# DMX512_6A.net
KiCad netlist of a schematic drawn in Altium Designer
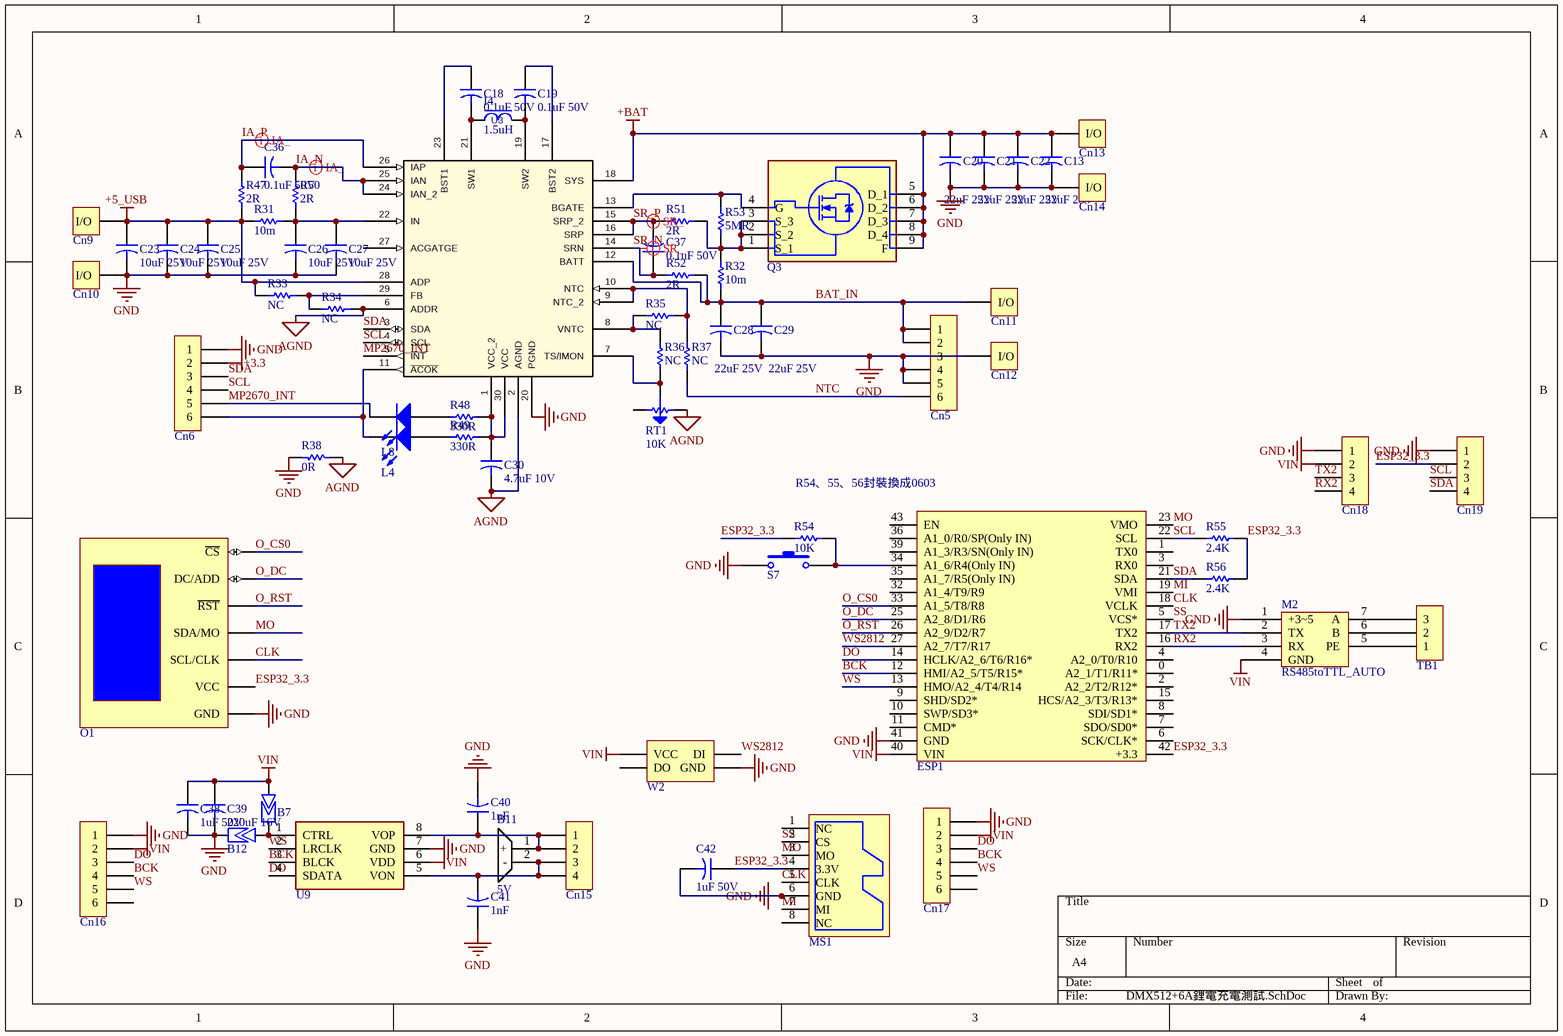
[diagram p0: DMX512+6A鋰電充電測試.SchDoc]

(export (version "E")
  (design (tool "Eeschema 10.0.6"))
  (components
    (comp (ref "B7")
      (value "不上錫")
      (footprint "BYPASS-0402")
      (description "短路焊點")
      (libsource (lib "MyLibray") (part "Bypass"))
    )
    (comp (ref "B11")
      (value "5V")
      (footprint "Buzzer_12085")
      (description "無源蜂鳴器")
      (libsource (lib "MyLibray") (part "Buzzer"))
    )
    (comp (ref "B12")
      (value "上錫")
      (footprint "BYPASS-0402")
      (description "短路焊點")
      (libsource (lib "MyLibray") (part "Bypass"))
    )
    (comp (ref "C13")
      (value "22uF 25V")
      (footprint "Cap SMD-0805")
      (description "電容")
      (libsource (lib "MyLibray") (part "Cap"))
    )
    (comp (ref "C18")
      (value "0.1uF 50V")
      (footprint "Cap SMD-0603")
      (description "電容")
      (libsource (lib "MyLibray") (part "Cap"))
    )
    (comp (ref "C19")
      (value "0.1uF 50V")
      (footprint "Cap SMD-0603")
      (description "電容")
      (libsource (lib "MyLibray") (part "Cap"))
    )
    (comp (ref "C20")
      (value "22uF 25V")
      (footprint "Cap SMD-0805")
      (description "電容")
      (libsource (lib "MyLibray") (part "Cap"))
    )
    (comp (ref "C21")
      (value "22uF 25V")
      (footprint "Cap SMD-0805")
      (description "電容")
      (libsource (lib "MyLibray") (part "Cap"))
    )
    (comp (ref "C22")
      (value "22uF 25V")
      (footprint "Cap SMD-0805")
      (description "電容")
      (libsource (lib "MyLibray") (part "Cap"))
    )
    (comp (ref "C23")
      (value "10uF 25V")
      (footprint "Cap SMD-0805")
      (description "電容")
      (libsource (lib "MyLibray") (part "Cap"))
    )
    (comp (ref "C24")
      (value "10uF 25V")
      (footprint "Cap SMD-0805")
      (description "電容")
      (libsource (lib "MyLibray") (part "Cap"))
    )
    (comp (ref "C25")
      (value "10uF 25V")
      (footprint "Cap SMD-0805")
      (description "電容")
      (libsource (lib "MyLibray") (part "Cap"))
    )
    (comp (ref "C26")
      (value "10uF 25V")
      (footprint "Cap SMD-0805")
      (description "電容")
      (libsource (lib "MyLibray") (part "Cap"))
    )
    (comp (ref "C27")
      (value "10uF 25V")
      (footprint "Cap SMD-0805")
      (description "電容")
      (libsource (lib "MyLibray") (part "Cap"))
    )
    (comp (ref "C28")
      (value "22uF 25V")
      (footprint "Cap SMD-0805")
      (description "電容")
      (libsource (lib "MyLibray") (part "Cap"))
    )
    (comp (ref "C29")
      (value "22uF 25V")
      (footprint "Cap SMD-0805")
      (description "電容")
      (libsource (lib "MyLibray") (part "Cap"))
    )
    (comp (ref "C30")
      (value "4.7uF 10V")
      (footprint "Cap SMD-0603")
      (description "電容")
      (libsource (lib "MyLibray") (part "Cap"))
    )
    (comp (ref "C36")
      (value "0.1uF 50V")
      (footprint "Cap SMD-0603")
      (description "電容")
      (libsource (lib "MyLibray") (part "Cap"))
    )
    (comp (ref "C37")
      (value "0.1uF 50V")
      (footprint "Cap SMD-0603")
      (description "電容")
      (libsource (lib "MyLibray") (part "Cap"))
    )
    (comp (ref "C38")
      (value "1uF 50V")
      (footprint "Cap SMD-0603")
      (description "電容")
      (libsource (lib "MyLibray") (part "Cap"))
    )
    (comp (ref "C39")
      (value "220uF 16V")
      (footprint "CAP SMD-B3528")
      (description "電容")
      (libsource (lib "MyLibray") (part "Cap"))
    )
    (comp (ref "C40")
      (value "1nF")
      (footprint "Cap SMD-0603")
      (description "電容")
      (libsource (lib "MyLibray") (part "Cap"))
    )
    (comp (ref "C41")
      (value "1nF")
      (footprint "Cap SMD-0603")
      (description "電容")
      (libsource (lib "MyLibray") (part "Cap"))
    )
    (comp (ref "C42")
      (value "1uF 50V")
      (footprint "Cap SMD-0603")
      (description "電容")
      (libsource (lib "MyLibray") (part "Cap"))
    )
    (comp (ref "Cn5")
      (value "KF2510-6")
      (footprint "KF2510-6A")
      (description "接線端子")
      (libsource (lib "") (part "Contact(6P)_1"))
    )
    (comp (ref "Cn6")
      (value "KF2510-6")
      (footprint "KF2510-6A")
      (description "接線端子")
      (libsource (lib "MyLibray") (part "Contact(6P)"))
    )
    (comp (ref "Cn9")
      (value "Contact")
      (footprint "Terminal_Screw")
      (description "接線端子、接點、郵票孔")
      (libsource (lib "") (part "Contact_1"))
    )
    (comp (ref "Cn10")
      (value "Contact")
      (footprint "Terminal_Screw")
      (description "接線端子、接點、郵票孔")
      (libsource (lib "") (part "Contact_1"))
    )
    (comp (ref "Cn11")
      (value "Contact")
      (footprint "Terminal_Screw")
      (description "接線端子、接點、郵票孔")
      (libsource (lib "MyLibray") (part "Contact"))
    )
    (comp (ref "Cn12")
      (value "Contact")
      (footprint "Terminal_Screw")
      (description "接線端子、接點、郵票孔")
      (libsource (lib "MyLibray") (part "Contact"))
    )
    (comp (ref "Cn13")
      (value "Contact")
      (footprint "Terminal_Screw")
      (description "接線端子、接點、郵票孔")
      (libsource (lib "MyLibray") (part "Contact"))
    )
    (comp (ref "Cn14")
      (value "Contact")
      (footprint "Terminal_Screw")
      (description "接線端子、接點、郵票孔")
      (libsource (lib "MyLibray") (part "Contact"))
    )
    (comp (ref "Cn15")
      (value "KF2510-4")
      (footprint "KF2510-4A")
      (description "接線端子")
      (libsource (lib "MyLibray") (part "Contact(4P)"))
    )
    (comp (ref "Cn16")
      (value "KF2510-6")
      (footprint "KF2510-6A")
      (description "接線端子")
      (libsource (lib "MyLibray") (part "Contact(6P)"))
    )
    (comp (ref "Cn17")
      (value "KF2510-6")
      (footprint "KF2510-6A")
      (description "接線端子")
      (libsource (lib "MyLibray") (part "Contact(6P)"))
    )
    (comp (ref "Cn18")
      (value "KF2510-4")
      (footprint "KF2510-4A")
      (description "接線端子")
      (libsource (lib "MyLibray") (part "Contact(4P)"))
    )
    (comp (ref "Cn19")
      (value "KF2510-4")
      (footprint "KF2510-4A")
      (description "接線端子")
      (libsource (lib "MyLibray") (part "Contact(4P)"))
    )
    (comp (ref "ESP1")
      (value "ESP32_Node32s")
      (footprint "ESP32 Module")
      (description "WIFI通訊模組")
      (libsource (lib "MyModule") (part "ESP32_Node32s"))
    )
    (comp (ref "I4")
      (value "1.5uH")
      (footprint "Inductor-1040")
      (description "一體成型電感")
      (libsource (lib "MyLibray") (part "Inductor"))
    )
    (comp (ref "L4")
      (value "藍")
      (footprint "LED SMD-0603")
      (description "LED")
      (libsource (lib "MyLibray") (part "LED"))
    )
    (comp (ref "L8")
      (value "藍")
      (footprint "LED SMD-0603")
      (description "LED")
      (libsource (lib "MyLibray") (part "LED"))
    )
    (comp (ref "M2")
      (value "RS485toTTL_AUTO")
      (footprint "RS485_AUTO MODULE")
      (description "TTLtoRS485")
      (libsource (lib "MyModule") (part "RS485toTTL_AUTO"))
    )
    (comp (ref "MS1")
      (value "SD Socket Micro")
      (footprint "SD  CARD SOCKET_Micro")
      (description "Micro SD 卡座")
      (libsource (lib "MyLibray") (part "SD Socket Micro"))
    )
    (comp (ref "O1")
      (value "排母 1*7P")
      (footprint "OLED-SPI/I2C")
      (description "OLED-SSD1306")
      (libsource (lib "MyModule") (part "OLED_SPI/I2C"))
    )
    (comp (ref "Q3")
      (value "BSC030N08NS5ATMA1")
      (footprint "TDSON-8")
      (description "場效電晶體_N")
      (fields (field (name "MOUSER2 PART NUMBER") "726-BSC030N08NS5ATMA"))
      (libsource (lib "MyLibray") (part "MOS_N_TDSON-8"))
    )
    (comp (ref "R31")
      (value "10m")
      (footprint "Res-0201")
      (description "電阻")
      (libsource (lib "MyLibray") (part "Res"))
    )
    (comp (ref "R32")
      (value "10m")
      (footprint "Res-0201")
      (description "電阻")
      (libsource (lib "MyLibray") (part "Res"))
    )
    (comp (ref "R33")
      (value "NC")
      (footprint "Res-0201")
      (description "電阻")
      (libsource (lib "MyLibray") (part "Res"))
    )
    (comp (ref "R34")
      (value "NC")
      (footprint "Res-0201")
      (description "電阻")
      (libsource (lib "MyLibray") (part "Res"))
    )
    (comp (ref "R35")
      (value "NC")
      (footprint "Res-0201")
      (description "電阻")
      (libsource (lib "MyLibray") (part "Res"))
    )
    (comp (ref "R36")
      (value "NC")
      (footprint "Res-0201")
      (description "電阻")
      (libsource (lib "MyLibray") (part "Res"))
    )
    (comp (ref "R37")
      (value "NC")
      (footprint "Res-0201")
      (description "電阻")
      (libsource (lib "MyLibray") (part "Res"))
    )
    (comp (ref "R38")
      (value "0R")
      (footprint "Res-0201")
      (description "電阻")
      (libsource (lib "MyLibray") (part "Res"))
    )
    (comp (ref "R47")
      (value "2R")
      (footprint "Res-0201")
      (description "電阻")
      (libsource (lib "MyLibray") (part "Res"))
    )
    (comp (ref "R48")
      (value "330R")
      (footprint "Res-0201")
      (description "電阻")
      (libsource (lib "MyLibray") (part "Res"))
    )
    (comp (ref "R49")
      (value "330R")
      (footprint "Res-0201")
      (description "電阻")
      (libsource (lib "MyLibray") (part "Res"))
    )
    (comp (ref "R50")
      (value "2R")
      (footprint "Res-0201")
      (description "電阻")
      (libsource (lib "MyLibray") (part "Res"))
    )
    (comp (ref "R51")
      (value "2R")
      (footprint "Res-0201")
      (description "電阻")
      (libsource (lib "MyLibray") (part "Res"))
    )
    (comp (ref "R52")
      (value "2R")
      (footprint "Res-0201")
      (description "電阻")
      (libsource (lib "MyLibray") (part "Res"))
    )
    (comp (ref "R53")
      (value "5MR")
      (footprint "Res-0201")
      (description "電阻")
      (libsource (lib "MyLibray") (part "Res"))
    )
    (comp (ref "R54")
      (value "10K")
      (footprint "Res-0201")
      (description "電阻")
      (libsource (lib "MyLibray") (part "Res"))
    )
    (comp (ref "R55")
      (value "2.4K")
      (footprint "Res-0201")
      (description "電阻")
      (libsource (lib "MyLibray") (part "Res"))
    )
    (comp (ref "R56")
      (value "2.4K")
      (footprint "Res-0201")
      (description "電阻")
      (libsource (lib "MyLibray") (part "Res"))
    )
    (comp (ref "RT1")
      (value "10K")
      (footprint "Res SMD-EVM3ESX50B")
      (description "電阻_可變")
      (libsource (lib "MyLibray") (part "Res-Tap"))
    )
    (comp (ref "S7")
      (value "Switch")
      (footprint "Switch SMD-3.6*6*2.5")
      (description "開關_按鍵")
      (libsource (lib "MyLibray") (part "Switch"))
    )
    (comp (ref "TB1")
      (value "HT508R-5.08 _3P")
      (footprint "Terminal block(KF2EDGR-5.08 _3P)")
      (description "端子台")
      (libsource (lib "MyLibray") (part "Terminal block(3P)"))
    )
    (comp (ref "U3")
      (value "MP2760GVT-010A")
      (footprint "TQFN-30_MP2760_MNP")
      (description "集成 NVDC 电源路径管理的1-4节电池升降压充电IC")
      (fields
        (field (name "MANUFACTURER_PART_NUMBER") "MP2760GVT-0000-P")
        (field (name "COPYRIGHT") "Copyright (C) 2023 Ultra Librarian. All rights reserved.")
      )
      (libsource (lib "MyLibray") (part "MP2760GVT"))
    )
    (comp (ref "U9")
      (value "NS4168")
      (footprint "SOP-8")
      (description "I2S音频功率放大器")
      (libsource (lib "MyLibray") (part "NS4168"))
    )
    (comp (ref "W2")
      (value "WS2812B")
      (footprint "LED SMD-WS2812B")
      (description "LED_可控燈珠")
      (libsource (lib "MyLibray") (part "WS2812B"))
    )
  )
  (nets
    (net (code "1") (name "+3.3") (class "Default")
      (node (ref "Cn6") (pin "2") (pinfunction "2_2") (pintype "passive"))
    )
    (net (code "2") (name "+5_USB") (class "Default")
      (node (ref "C23") (pin "1") (pinfunction "1_1") (pintype "passive"))
      (node (ref "C24") (pin "1") (pinfunction "1_1") (pintype "passive"))
      (node (ref "C25") (pin "1") (pinfunction "1_1") (pintype "passive"))
      (node (ref "Cn9") (pin "1") (pinfunction "I/O_1") (pintype "passive"))
      (node (ref "R31") (pin "1") (pinfunction "1_1") (pintype "passive"))
      (node (ref "R33") (pin "1") (pinfunction "1_1") (pintype "passive"))
      (node (ref "R47") (pin "1") (pinfunction "1_1") (pintype "passive"))
      (node (ref "U3") (pin "28") (pinfunction "ADP_28") (pintype "passive"))
    )
    (net (code "3") (name "+BAT") (class "Default")
      (node (ref "C13") (pin "1") (pinfunction "1_1") (pintype "passive"))
      (node (ref "C20") (pin "1") (pinfunction "1_1") (pintype "passive"))
      (node (ref "C21") (pin "1") (pinfunction "1_1") (pintype "passive"))
      (node (ref "C22") (pin "1") (pinfunction "1_1") (pintype "passive"))
      (node (ref "Cn13") (pin "1") (pinfunction "I/O_1") (pintype "passive"))
      (node (ref "Q3") (pin "5") (pinfunction "D_1_5") (pintype "passive"))
      (node (ref "Q3") (pin "6") (pinfunction "D_2_6") (pintype "passive"))
      (node (ref "Q3") (pin "7") (pinfunction "D_3_7") (pintype "passive"))
      (node (ref "Q3") (pin "8") (pinfunction "D_4_8") (pintype "passive"))
      (node (ref "Q3") (pin "9") (pinfunction "F_9") (pintype "passive"))
      (node (ref "U3") (pin "18") (pinfunction "SYS_18") (pintype "power_in"))
    )
    (net (code "4") (name "/BAT_IN") (class "Default")
      (node (ref "C28") (pin "1") (pinfunction "1_1") (pintype "passive"))
      (node (ref "C29") (pin "1") (pinfunction "1_1") (pintype "passive"))
      (node (ref "Cn11") (pin "1") (pinfunction "I/O_1") (pintype "passive"))
      (node (ref "Cn5") (pin "1") (pinfunction "1_1") (pintype "passive"))
      (node (ref "Cn5") (pin "2") (pinfunction "2_2") (pintype "passive"))
      (node (ref "R32") (pin "1") (pinfunction "1_1") (pintype "passive"))
      (node (ref "R52") (pin "1") (pinfunction "1_1") (pintype "passive"))
      (node (ref "U3") (pin "12") (pinfunction "BATT_12") (pintype "power_in"))
    )
    (net (code "5") (name "/BCK") (class "Default")
      (node (ref "Cn16") (pin "4") (pinfunction "4_4") (pintype "passive"))
      (node (ref "Cn17") (pin "4") (pinfunction "4_4") (pintype "passive"))
      (node (ref "ESP1") (pin "12") (pinfunction "HMI/A2_5/T5/R15*_12") (pintype "passive"))
      (node (ref "U9") (pin "3") (pinfunction "BLCK_3") (pintype "passive"))
    )
    (net (code "6") (name "/CLK") (class "Default")
      (node (ref "ESP1") (pin "18") (pinfunction "VCLK_18") (pintype "passive"))
      (node (ref "MS1") (pin "5") (pinfunction "CLK_5") (pintype "passive"))
      (node (ref "O1") (pin "3") (pinfunction "SCL/CLK_3") (pintype "passive"))
    )
    (net (code "7") (name "/DO") (class "Default")
      (node (ref "Cn16") (pin "3") (pinfunction "3_3") (pintype "passive"))
      (node (ref "Cn17") (pin "3") (pinfunction "3_3") (pintype "passive"))
      (node (ref "ESP1") (pin "14") (pinfunction "HCLK/A2_6/T6/R16*_14") (pintype "passive"))
      (node (ref "U9") (pin "4") (pinfunction "SDATA_4") (pintype "passive"))
    )
    (net (code "8") (name "/ESP32_3.3") (class "Default")
      (node (ref "C42") (pin "1") (pinfunction "1_1") (pintype "passive"))
      (node (ref "Cn19") (pin "2") (pinfunction "2_2") (pintype "passive"))
      (node (ref "ESP1") (pin "42") (pinfunction "+3.3_42") (pintype "passive"))
      (node (ref "MS1") (pin "4") (pinfunction "3.3V_4") (pintype "power_in"))
      (node (ref "O1") (pin "2") (pinfunction "VCC_2") (pintype "power_in"))
      (node (ref "R54") (pin "1") (pinfunction "1_1") (pintype "passive"))
      (node (ref "R55") (pin "2") (pinfunction "2_2") (pintype "passive"))
      (node (ref "R56") (pin "2") (pinfunction "2_2") (pintype "passive"))
    )
    (net (code "9") (name "/IA_N") (class "Default")
      (node (ref "C36") (pin "2") (pinfunction "2_2") (pintype "passive"))
      (node (ref "R50") (pin "2") (pinfunction "2_2") (pintype "passive"))
      (node (ref "U3") (pin "24") (pinfunction "IAN_2_24") (pintype "input"))
      (node (ref "U3") (pin "25") (pinfunction "IAN_25") (pintype "input"))
    )
    (net (code "10") (name "/IA_P") (class "Default")
      (node (ref "C36") (pin "1") (pinfunction "1_1") (pintype "passive"))
      (node (ref "R47") (pin "2") (pinfunction "2_2") (pintype "passive"))
      (node (ref "U3") (pin "26") (pinfunction "IAP_26") (pintype "input"))
    )
    (net (code "11") (name "/MI") (class "Default")
      (node (ref "ESP1") (pin "19") (pinfunction "VMI_19") (pintype "passive"))
      (node (ref "MS1") (pin "7") (pinfunction "MI_7") (pintype "passive"))
    )
    (net (code "12") (name "/MO") (class "Default")
      (node (ref "ESP1") (pin "23") (pinfunction "VMO_23") (pintype "passive"))
      (node (ref "MS1") (pin "3") (pinfunction "MO_3") (pintype "passive"))
      (node (ref "O1") (pin "4") (pinfunction "SDA/MO_4") (pintype "passive"))
    )
    (net (code "13") (name "/MP2670_INT") (class "Default")
      (node (ref "Cn6") (pin "5") (pinfunction "5_5") (pintype "passive"))
      (node (ref "L8") (pin "1") (pinfunction "K_1") (pintype "passive"))
      (node (ref "U3") (pin "5") (pinfunction "~{INT}_5") (pintype "output"))
    )
    (net (code "14") (name "/NTC") (class "Default")
      (node (ref "Cn5") (pin "6") (pinfunction "6_6") (pintype "passive"))
      (node (ref "R37") (pin "1") (pinfunction "1_1") (pintype "passive"))
    )
    (net (code "15") (name "/O_CS0") (class "Default")
      (node (ref "ESP1") (pin "33") (pinfunction "A1_5/T8/R8_33") (pintype "passive"))
      (node (ref "O1") (pin "7") (pinfunction "~{CS}_7") (pintype "bidirectional"))
    )
    (net (code "16") (name "/O_DC") (class "Default")
      (node (ref "ESP1") (pin "25") (pinfunction "A2_8/D1/R6_25") (pintype "passive"))
      (node (ref "O1") (pin "6") (pinfunction "DC/ADD_6") (pintype "bidirectional"))
    )
    (net (code "17") (name "/O_RST") (class "Default")
      (node (ref "ESP1") (pin "26") (pinfunction "A2_9/D2/R7_26") (pintype "passive"))
      (node (ref "O1") (pin "5") (pinfunction "~{RST}_5") (pintype "passive"))
    )
    (net (code "18") (name "/RX2") (class "Default")
      (node (ref "Cn18") (pin "4") (pinfunction "4_4") (pintype "passive"))
      (node (ref "ESP1") (pin "16") (pinfunction "RX2_16") (pintype "passive"))
      (node (ref "M2") (pin "3") (pinfunction "RX_3") (pintype "passive"))
    )
    (net (code "19") (name "/SCL") (class "Default")
      (node (ref "Cn19") (pin "3") (pinfunction "3_3") (pintype "passive"))
      (node (ref "Cn6") (pin "4") (pinfunction "4_4") (pintype "passive"))
      (node (ref "ESP1") (pin "22") (pinfunction "SCL_22") (pintype "passive"))
      (node (ref "R55") (pin "1") (pinfunction "1_1") (pintype "passive"))
      (node (ref "U3") (pin "4") (pinfunction "SCL_4") (pintype "bidirectional"))
    )
    (net (code "20") (name "/SDA") (class "Default")
      (node (ref "Cn19") (pin "4") (pinfunction "4_4") (pintype "passive"))
      (node (ref "Cn6") (pin "3") (pinfunction "3_3") (pintype "passive"))
      (node (ref "ESP1") (pin "21") (pinfunction "SDA_21") (pintype "passive"))
      (node (ref "R56") (pin "1") (pinfunction "1_1") (pintype "passive"))
      (node (ref "U3") (pin "3") (pinfunction "SDA_3") (pintype "bidirectional"))
    )
    (net (code "21") (name "/SR_N") (class "Default")
      (node (ref "C37") (pin "1") (pinfunction "1_1") (pintype "passive"))
      (node (ref "R52") (pin "2") (pinfunction "2_2") (pintype "passive"))
      (node (ref "U3") (pin "14") (pinfunction "SRN_14") (pintype "passive"))
    )
    (net (code "22") (name "/SR_P") (class "Default")
      (node (ref "C37") (pin "2") (pinfunction "2_2") (pintype "passive"))
      (node (ref "R51") (pin "2") (pinfunction "2_2") (pintype "passive"))
      (node (ref "U3") (pin "15") (pinfunction "SRP_2_15") (pintype "passive"))
      (node (ref "U3") (pin "16") (pinfunction "SRP_16") (pintype "passive"))
    )
    (net (code "23") (name "/SS") (class "Default")
      (node (ref "ESP1") (pin "5") (pinfunction "VCS*_5") (pintype "passive"))
      (node (ref "MS1") (pin "2") (pinfunction "CS_2") (pintype "passive"))
    )
    (net (code "24") (name "/TX2") (class "Default")
      (node (ref "Cn18") (pin "3") (pinfunction "3_3") (pintype "passive"))
      (node (ref "ESP1") (pin "17") (pinfunction "TX2_17") (pintype "passive"))
      (node (ref "M2") (pin "2") (pinfunction "TX_2") (pintype "passive"))
    )
    (net (code "25") (name "/WS") (class "Default")
      (node (ref "Cn16") (pin "5") (pinfunction "5_5") (pintype "passive"))
      (node (ref "Cn17") (pin "5") (pinfunction "5_5") (pintype "passive"))
      (node (ref "ESP1") (pin "13") (pinfunction "HMO/A2_4/T4/R14_13") (pintype "passive"))
      (node (ref "U9") (pin "2") (pinfunction "LRCLK_2") (pintype "passive"))
    )
    (net (code "26") (name "/WS2812") (class "Default")
      (node (ref "ESP1") (pin "27") (pinfunction "A2_7/T7/R17_27") (pintype "passive"))
      (node (ref "W2") (pin "4") (pinfunction "DI_4") (pintype "passive"))
    )
    (net (code "27") (name "AGND") (class "Default")
      (node (ref "C30") (pin "2") (pinfunction "2_2") (pintype "passive"))
      (node (ref "R34") (pin "2") (pinfunction "2_2") (pintype "passive"))
      (node (ref "R38") (pin "2") (pinfunction "2_2") (pintype "passive"))
      (node (ref "RT1") (pin "1") (pinfunction "1_1") (pintype "passive"))
      (node (ref "U3") (pin "2") (pinfunction "AGND_2") (pintype "power_in"))
      (node (ref "U3") (pin "6") (pinfunction "ADDR_6") (pintype "passive"))
    )
    (net (code "28") (name "GND") (class "Default")
      (node (ref "B12") (pin "1") (pinfunction "1_1") (pintype "passive"))
      (node (ref "C13") (pin "2") (pinfunction "2_2") (pintype "passive"))
      (node (ref "C20") (pin "2") (pinfunction "2_2") (pintype "passive"))
      (node (ref "C21") (pin "2") (pinfunction "2_2") (pintype "passive"))
      (node (ref "C22") (pin "2") (pinfunction "2_2") (pintype "passive"))
      (node (ref "C23") (pin "2") (pinfunction "2_2") (pintype "passive"))
      (node (ref "C24") (pin "2") (pinfunction "2_2") (pintype "passive"))
      (node (ref "C25") (pin "2") (pinfunction "2_2") (pintype "passive"))
      (node (ref "C26") (pin "2") (pinfunction "2_2") (pintype "passive"))
      (node (ref "C27") (pin "2") (pinfunction "2_2") (pintype "passive"))
      (node (ref "C28") (pin "2") (pinfunction "2_2") (pintype "passive"))
      (node (ref "C29") (pin "2") (pinfunction "2_2") (pintype "passive"))
      (node (ref "C38") (pin "2") (pinfunction "2_2") (pintype "passive"))
      (node (ref "C39") (pin "2") (pinfunction "2_2") (pintype "passive"))
      (node (ref "C40") (pin "2") (pinfunction "2_2") (pintype "passive"))
      (node (ref "C41") (pin "1") (pinfunction "1_1") (pintype "passive"))
      (node (ref "C42") (pin "2") (pinfunction "2_2") (pintype "passive"))
      (node (ref "Cn10") (pin "1") (pinfunction "I/O_1") (pintype "passive"))
      (node (ref "Cn12") (pin "1") (pinfunction "I/O_1") (pintype "passive"))
      (node (ref "Cn14") (pin "1") (pinfunction "I/O_1") (pintype "passive"))
      (node (ref "Cn16") (pin "1") (pinfunction "1_1") (pintype "passive"))
      (node (ref "Cn17") (pin "1") (pinfunction "1_1") (pintype "passive"))
      (node (ref "Cn18") (pin "1") (pinfunction "1_1") (pintype "passive"))
      (node (ref "Cn19") (pin "1") (pinfunction "1_1") (pintype "passive"))
      (node (ref "Cn5") (pin "3") (pinfunction "3_3") (pintype "passive"))
      (node (ref "Cn5") (pin "4") (pinfunction "4_4") (pintype "passive"))
      (node (ref "Cn5") (pin "5") (pinfunction "5_5") (pintype "passive"))
      (node (ref "Cn6") (pin "1") (pinfunction "1_1") (pintype "passive"))
      (node (ref "ESP1") (pin "41") (pinfunction "GND_41") (pintype "power_in"))
      (node (ref "M2") (pin "1") (pinfunction "+3~5_1") (pintype "passive"))
      (node (ref "MS1") (pin "6") (pinfunction "GND_6") (pintype "power_in"))
      (node (ref "O1") (pin "1") (pinfunction "GND_1") (pintype "power_in"))
      (node (ref "R38") (pin "1") (pinfunction "1_1") (pintype "passive"))
      (node (ref "S7") (pin "1") (pinfunction "1_1") (pintype "passive"))
      (node (ref "U3") (pin "20") (pinfunction "PGND_20") (pintype "power_in"))
      (node (ref "U9") (pin "7") (pinfunction "GND_7") (pintype "passive"))
      (node (ref "W2") (pin "3") (pinfunction "GND_3") (pintype "power_in"))
    )
    (net (code "29") (name "Net-(B11-+)") (class "Default")
      (node (ref "B11") (pin "1") (pinfunction "+_1") (pintype "passive"))
      (node (ref "C40") (pin "1") (pinfunction "1_1") (pintype "passive"))
      (node (ref "Cn15") (pin "1") (pinfunction "1_1") (pintype "passive"))
      (node (ref "Cn15") (pin "2") (pinfunction "2_2") (pintype "passive"))
      (node (ref "U9") (pin "8") (pinfunction "VOP_8") (pintype "passive"))
    )
    (net (code "30") (name "Net-(B11--)") (class "Default")
      (node (ref "B11") (pin "2") (pinfunction "-_2") (pintype "passive"))
      (node (ref "C41") (pin "2") (pinfunction "2_2") (pintype "passive"))
      (node (ref "Cn15") (pin "3") (pinfunction "3_3") (pintype "passive"))
      (node (ref "Cn15") (pin "4") (pinfunction "4_4") (pintype "passive"))
      (node (ref "U9") (pin "5") (pinfunction "VON_5") (pintype "passive"))
    )
    (net (code "31") (name "Net-(ESP1-A1_6{slash}R4(Only_IN))") (class "Default")
      (node (ref "ESP1") (pin "34") (pinfunction "A1_6/R4(Only_IN)_34") (pintype "passive"))
      (node (ref "R54") (pin "2") (pinfunction "2_2") (pintype "passive"))
      (node (ref "S7") (pin "2") (pinfunction "2_2") (pintype "passive"))
    )
    (net (code "32") (name "Net-(L4-A)") (class "Default")
      (node (ref "L4") (pin "2") (pinfunction "A_2") (pintype "passive"))
      (node (ref "R49") (pin "1") (pinfunction "1_1") (pintype "passive"))
    )
    (net (code "33") (name "Net-(L4-K)") (class "Default")
      (node (ref "Cn6") (pin "6") (pinfunction "6_6") (pintype "passive"))
      (node (ref "L4") (pin "1") (pinfunction "K_1") (pintype "passive"))
      (node (ref "U3") (pin "11") (pinfunction "~{ACOK}_11") (pintype "output"))
    )
    (net (code "34") (name "Net-(L8-A)") (class "Default")
      (node (ref "L8") (pin "2") (pinfunction "A_2") (pintype "passive"))
      (node (ref "R48") (pin "2") (pinfunction "2_2") (pintype "passive"))
    )
    (net (code "35") (name "Net-(M2-A)") (class "Default")
      (node (ref "M2") (pin "7") (pinfunction "A_7") (pintype "passive"))
      (node (ref "TB1") (pin "3") (pinfunction "3_3") (pintype "passive"))
    )
    (net (code "36") (name "Net-(M2-B)") (class "Default")
      (node (ref "M2") (pin "6") (pinfunction "B_6") (pintype "passive"))
      (node (ref "TB1") (pin "2") (pinfunction "2_2") (pintype "passive"))
    )
    (net (code "37") (name "Net-(M2-PE)") (class "Default")
      (node (ref "M2") (pin "5") (pinfunction "PE_5") (pintype "passive"))
      (node (ref "TB1") (pin "1") (pinfunction "1_1") (pintype "passive"))
    )
    (net (code "38") (name "Net-(Q3-G)") (class "Default")
      (node (ref "Q3") (pin "4") (pinfunction "G_4") (pintype "passive"))
      (node (ref "R53") (pin "2") (pinfunction "2_2") (pintype "passive"))
      (node (ref "U3") (pin "13") (pinfunction "BGATE_13") (pintype "passive"))
    )
    (net (code "39") (name "Net-(Q3-S_1)") (class "Default")
      (node (ref "Q3") (pin "1") (pinfunction "S_1_1") (pintype "passive"))
      (node (ref "Q3") (pin "2") (pinfunction "S_2_2") (pintype "passive"))
      (node (ref "Q3") (pin "3") (pinfunction "S_3_3") (pintype "passive"))
      (node (ref "R32") (pin "2") (pinfunction "2_2") (pintype "passive"))
      (node (ref "R51") (pin "1") (pinfunction "1_1") (pintype "passive"))
      (node (ref "R53") (pin "1") (pinfunction "1_1") (pintype "passive"))
    )
    (net (code "40") (name "Net-(RT1-TAP)") (class "Default")
      (node (ref "R36") (pin "1") (pinfunction "1_1") (pintype "passive"))
      (node (ref "RT1") (pin "3") (pinfunction "TAP_3") (pintype "passive"))
      (node (ref "U3") (pin "7") (pinfunction "TS/IMON_7") (pintype "passive"))
    )
    (net (code "41") (name "Net-(U3-BST1)") (class "Default")
      (node (ref "C18") (pin "1") (pinfunction "1_1") (pintype "passive"))
      (node (ref "U3") (pin "23") (pinfunction "BST1_23") (pintype "power_in"))
    )
    (net (code "42") (name "Net-(U3-BST2)") (class "Default")
      (node (ref "C19") (pin "1") (pinfunction "1_1") (pintype "passive"))
      (node (ref "U3") (pin "17") (pinfunction "BST2_17") (pintype "power_in"))
    )
    (net (code "43") (name "Net-(U3-FB)") (class "Default")
      (node (ref "R33") (pin "2") (pinfunction "2_2") (pintype "passive"))
      (node (ref "R34") (pin "1") (pinfunction "1_1") (pintype "passive"))
      (node (ref "U3") (pin "29") (pinfunction "FB_29") (pintype "passive"))
    )
    (net (code "44") (name "Net-(U3-IN)") (class "Default")
      (node (ref "C26") (pin "1") (pinfunction "1_1") (pintype "passive"))
      (node (ref "C27") (pin "1") (pinfunction "1_1") (pintype "passive"))
      (node (ref "R31") (pin "2") (pinfunction "2_2") (pintype "passive"))
      (node (ref "R50") (pin "1") (pinfunction "1_1") (pintype "passive"))
      (node (ref "U3") (pin "22") (pinfunction "IN_22") (pintype "input"))
    )
    (net (code "45") (name "Net-(U3-NTC)") (class "Default")
      (node (ref "R35") (pin "2") (pinfunction "2_2") (pintype "passive"))
      (node (ref "R37") (pin "2") (pinfunction "2_2") (pintype "passive"))
      (node (ref "U3") (pin "10") (pinfunction "NTC_10") (pintype "input"))
      (node (ref "U3") (pin "9") (pinfunction "NTC_2_9") (pintype "input"))
    )
    (net (code "46") (name "Net-(U3-SW1)") (class "Default")
      (node (ref "C18") (pin "2") (pinfunction "2_2") (pintype "passive"))
      (node (ref "I4") (pin "1") (pinfunction "1_1") (pintype "passive"))
      (node (ref "U3") (pin "21") (pinfunction "SW1_21") (pintype "passive"))
    )
    (net (code "47") (name "Net-(U3-SW2)") (class "Default")
      (node (ref "C19") (pin "2") (pinfunction "2_2") (pintype "passive"))
      (node (ref "I4") (pin "2") (pinfunction "2_2") (pintype "passive"))
      (node (ref "U3") (pin "19") (pinfunction "SW2_19") (pintype "passive"))
    )
    (net (code "48") (name "Net-(U3-VCC)") (class "Default")
      (node (ref "C30") (pin "1") (pinfunction "1_1") (pintype "passive"))
      (node (ref "R48") (pin "1") (pinfunction "1_1") (pintype "passive"))
      (node (ref "R49") (pin "2") (pinfunction "2_2") (pintype "passive"))
      (node (ref "U3") (pin "1") (pinfunction "VCC_2_1") (pintype "power_in"))
      (node (ref "U3") (pin "30") (pinfunction "VCC_30") (pintype "power_in"))
    )
    (net (code "49") (name "Net-(U3-VNTC)") (class "Default")
      (node (ref "R35") (pin "1") (pinfunction "1_1") (pintype "passive"))
      (node (ref "R36") (pin "2") (pinfunction "2_2") (pintype "passive"))
      (node (ref "U3") (pin "8") (pinfunction "VNTC_8") (pintype "passive"))
    )
    (net (code "50") (name "Net-(U9-CTRL)") (class "Default")
      (node (ref "B12") (pin "2") (pinfunction "2_2") (pintype "passive"))
      (node (ref "B7") (pin "1") (pinfunction "1_1") (pintype "passive"))
      (node (ref "U9") (pin "1") (pinfunction "CTRL_1") (pintype "passive"))
    )
    (net (code "51") (name "VIN") (class "Default")
      (node (ref "B7") (pin "2") (pinfunction "2_2") (pintype "passive"))
      (node (ref "C38") (pin "1") (pinfunction "1_1") (pintype "passive"))
      (node (ref "C39") (pin "1") (pinfunction "1_1") (pintype "passive"))
      (node (ref "Cn16") (pin "2") (pinfunction "2_2") (pintype "passive"))
      (node (ref "Cn17") (pin "2") (pinfunction "2_2") (pintype "passive"))
      (node (ref "Cn18") (pin "2") (pinfunction "2_2") (pintype "passive"))
      (node (ref "ESP1") (pin "40") (pinfunction "VIN_40") (pintype "passive"))
      (node (ref "M2") (pin "4") (pinfunction "GND_4") (pintype "passive"))
      (node (ref "U9") (pin "6") (pinfunction "VDD_6") (pintype "passive"))
      (node (ref "W2") (pin "1") (pinfunction "VCC_1") (pintype "power_in"))
    )
    (net (code "52") (name "unconnected-(Cn16-Pad6)") (class "Default")
      (node (ref "Cn16") (pin "6") (pinfunction "6_6") (pintype "passive"))
    )
    (net (code "53") (name "unconnected-(Cn17-Pad6)") (class "Default")
      (node (ref "Cn17") (pin "6") (pinfunction "6_6") (pintype "passive"))
    )
    (net (code "54") (name "unconnected-(ESP1-A1_0{slash}R0{slash}SP(Only_IN)-Pad36)") (class "Default")
      (node (ref "ESP1") (pin "36") (pinfunction "A1_0/R0/SP(Only_IN)_36") (pintype "passive"))
    )
    (net (code "55") (name "unconnected-(ESP1-A1_3{slash}R3{slash}SN(Only_IN)-Pad39)") (class "Default")
      (node (ref "ESP1") (pin "39") (pinfunction "A1_3/R3/SN(Only_IN)_39") (pintype "passive"))
    )
    (net (code "56") (name "unconnected-(ESP1-A1_4{slash}T9{slash}R9-Pad32)") (class "Default")
      (node (ref "ESP1") (pin "32") (pinfunction "A1_4/T9/R9_32") (pintype "passive"))
    )
    (net (code "57") (name "unconnected-(ESP1-A1_7{slash}R5(Only_IN)-Pad35)") (class "Default")
      (node (ref "ESP1") (pin "35") (pinfunction "A1_7/R5(Only_IN)_35") (pintype "passive"))
    )
    (net (code "58") (name "unconnected-(ESP1-A2_0{slash}T0{slash}R10-Pad4)") (class "Default")
      (node (ref "ESP1") (pin "4") (pinfunction "A2_0/T0/R10_4") (pintype "passive"))
    )
    (net (code "59") (name "unconnected-(ESP1-A2_1{slash}T1{slash}R11*-Pad0)") (class "Default")
      (node (ref "ESP1") (pin "0") (pinfunction "A2_1/T1/R11*_0") (pintype "passive"))
    )
    (net (code "60") (name "unconnected-(ESP1-A2_2{slash}T2{slash}R12*-Pad2)") (class "Default")
      (node (ref "ESP1") (pin "2") (pinfunction "A2_2/T2/R12*_2") (pintype "passive"))
    )
    (net (code "61") (name "unconnected-(ESP1-CMD*-Pad11)") (class "Default")
      (node (ref "ESP1") (pin "11") (pinfunction "CMD*_11") (pintype "passive"))
    )
    (net (code "62") (name "unconnected-(ESP1-EN-Pad43)") (class "Default")
      (node (ref "ESP1") (pin "43") (pinfunction "EN_43") (pintype "passive"))
    )
    (net (code "63") (name "unconnected-(ESP1-HCS{slash}A2_3{slash}T3{slash}R13*-Pad15)") (class "Default")
      (node (ref "ESP1") (pin "15") (pinfunction "HCS/A2_3/T3/R13*_15") (pintype "passive"))
    )
    (net (code "64") (name "unconnected-(ESP1-RX0-Pad3)") (class "Default")
      (node (ref "ESP1") (pin "3") (pinfunction "RX0_3") (pintype "passive"))
    )
    (net (code "65") (name "unconnected-(ESP1-SCK{slash}CLK*-Pad6)") (class "Default")
      (node (ref "ESP1") (pin "6") (pinfunction "SCK/CLK*_6") (pintype "passive"))
    )
    (net (code "66") (name "unconnected-(ESP1-SDI{slash}SD1*-Pad8)") (class "Default")
      (node (ref "ESP1") (pin "8") (pinfunction "SDI/SD1*_8") (pintype "passive"))
    )
    (net (code "67") (name "unconnected-(ESP1-SDO{slash}SD0*-Pad7)") (class "Default")
      (node (ref "ESP1") (pin "7") (pinfunction "SDO/SD0*_7") (pintype "passive"))
    )
    (net (code "68") (name "unconnected-(ESP1-SHD{slash}SD2*-Pad9)") (class "Default")
      (node (ref "ESP1") (pin "9") (pinfunction "SHD/SD2*_9") (pintype "passive"))
    )
    (net (code "69") (name "unconnected-(ESP1-SWP{slash}SD3*-Pad10)") (class "Default")
      (node (ref "ESP1") (pin "10") (pinfunction "SWP/SD3*_10") (pintype "passive"))
    )
    (net (code "70") (name "unconnected-(ESP1-TX0-Pad1)") (class "Default")
      (node (ref "ESP1") (pin "1") (pinfunction "TX0_1") (pintype "passive"))
    )
    (net (code "71") (name "unconnected-(MS1-NC-Pad1)") (class "Default")
      (node (ref "MS1") (pin "1") (pinfunction "NC_1") (pintype "passive"))
    )
    (net (code "72") (name "unconnected-(MS1-NC-Pad8)") (class "Default")
      (node (ref "MS1") (pin "8") (pinfunction "NC_8") (pintype "passive"))
    )
    (net (code "73") (name "unconnected-(RT1-Pad2)") (class "Default")
      (node (ref "RT1") (pin "2") (pinfunction "2_2") (pintype "passive"))
    )
    (net (code "74") (name "unconnected-(U3-ACGATGE-Pad27)") (class "Default")
      (node (ref "U3") (pin "27") (pinfunction "ACGATGE_27") (pintype "input"))
    )
    (net (code "75") (name "unconnected-(W2-DO-Pad2)") (class "Default")
      (node (ref "W2") (pin "2") (pinfunction "DO_2") (pintype "passive"))
    )
  )
)
